# TMP235AQDB2TQ1.net
KiCad netlist of a schematic drawn in Altium Designer
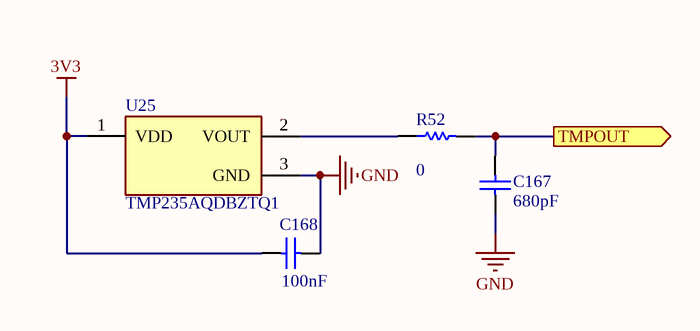
[diagram p0: TMP235AQDB2TQ1.SchDoc]

(export (version "E")
  (design (tool "Eeschema 10.0.6"))
  (components
    (comp (ref "C167")
      (value "680pF")
      (footprint "1608[0603]")
      (description "Capacitor")
      (fields (field (name "Comment") "Cap") (field (name "PUBLISHER") "Altium Limited"))
      (libsource (lib "Miscellaneous Devices") (part "Cap"))
    )
    (comp (ref "C168")
      (value "100nF")
      (footprint "0402-A")
      (description "Capacitor")
      (fields (field (name "Comment") "Cap") (field (name "PUBLISHER") "Altium Limited"))
      (libsource (lib "Miscellaneous Devices") (part "Cap"))
    )
    (comp (ref "R52")
      (value "0")
      (footprint "0402-A")
      (description "Resistor")
      (fields (field (name "Comment") "Res1") (field (name "PUBLISHER") "Altium Limited"))
      (libsource (lib "Miscellaneous Devices") (part "Res1"))
    )
    (comp (ref "U25")
      (value "TMP235AQDBZTQ1")
      (footprint "FP-DBZ0003A-MFG")
      (description "LOW-POWER HIGH-ACCURACY ANALOG O")
      (fields
        (field (name "MANUFACTURER") "Texas Instruments")
        (field (name "MANUFACTURER PART NUMBER") "TMP235A2DBZR")
      )
      (libsource (lib "Altium Content Vault") (part "1212246baba8f64ab0dd7b63bd818eb"))
    )
  )
  (nets
    (net (code "1") (name "/TMPOUT") (class "Default")
      (node (ref "C167") (pin "1") (pinfunction "1_1") (pintype "passive"))
      (node (ref "R52") (pin "2") (pinfunction "2_2") (pintype "passive"))
    )
    (net (code "2") (name "3V3") (class "Default")
      (node (ref "C168") (pin "1") (pinfunction "1_1") (pintype "passive"))
      (node (ref "U25") (pin "1") (pinfunction "VDD_1") (pintype "power_in"))
    )
    (net (code "3") (name "GND") (class "Default")
      (node (ref "C167") (pin "2") (pinfunction "2_2") (pintype "passive"))
      (node (ref "C168") (pin "2") (pinfunction "2_2") (pintype "passive"))
      (node (ref "U25") (pin "3") (pinfunction "GND_3") (pintype "power_in"))
    )
    (net (code "4") (name "Net-(U25-VOUT)") (class "Default")
      (node (ref "R52") (pin "1") (pinfunction "1_1") (pintype "passive"))
      (node (ref "U25") (pin "2") (pinfunction "VOUT_2") (pintype "passive"))
    )
  )
)
